# STM32-ROMI_Rev_A_1_STM32.net
KiCad netlist of a schematic drawn in Altium Designer
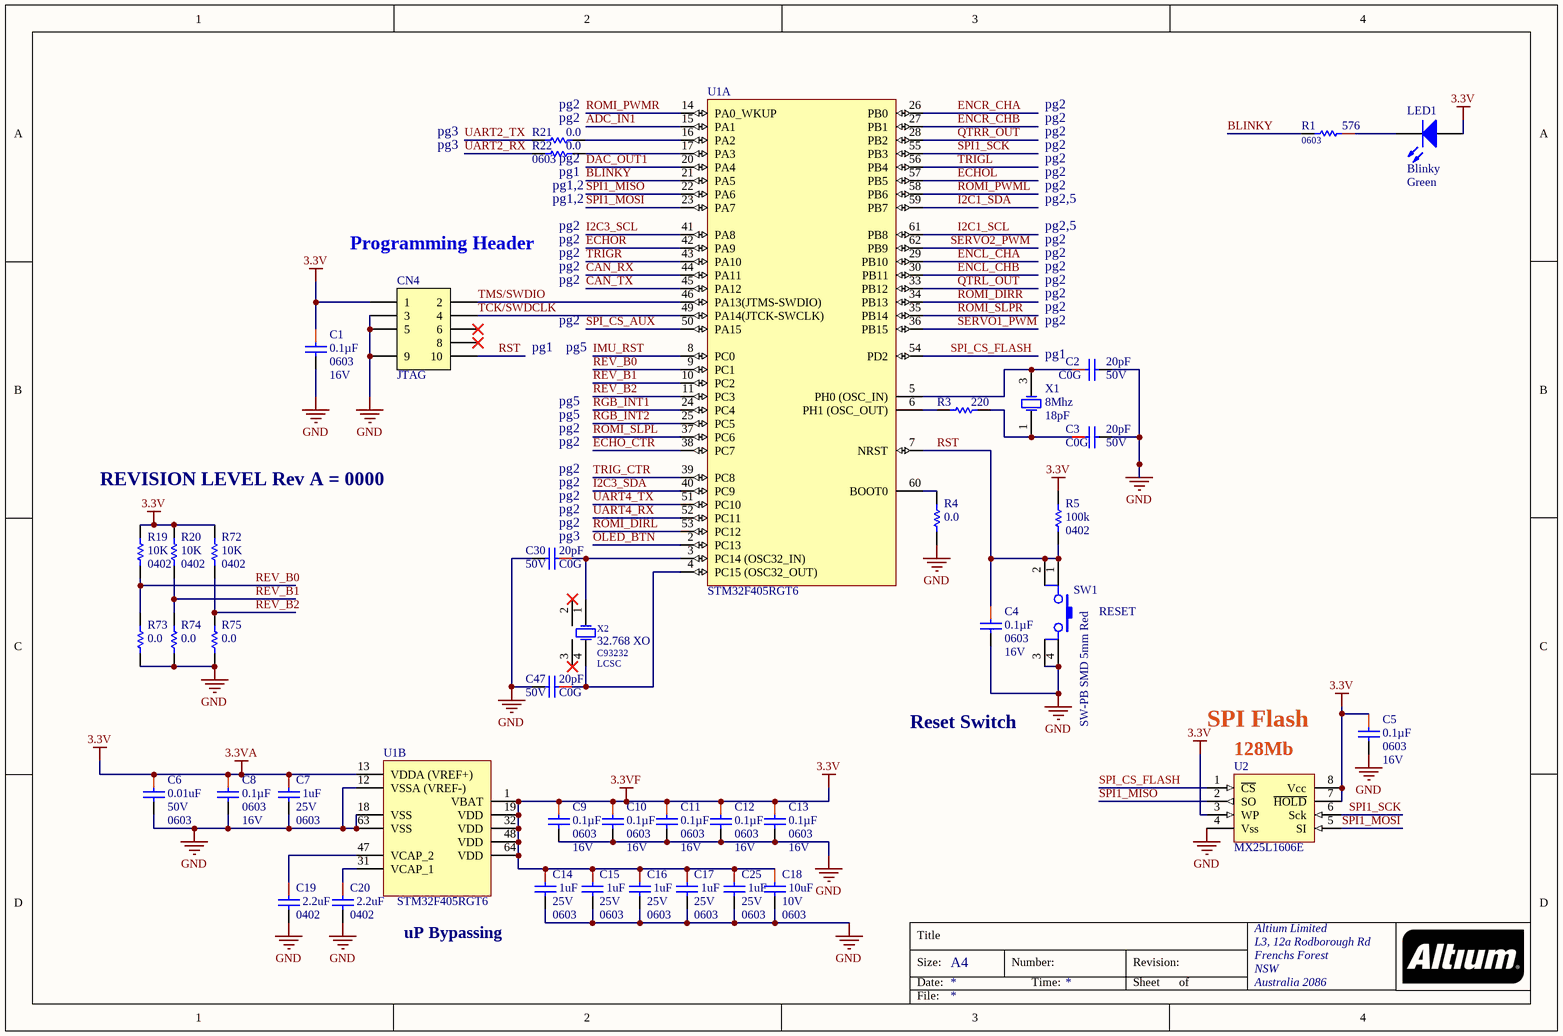
[diagram p0: STM32-ROMI_Rev_A_1_STM32.SchDoc]

(export (version "E")
  (design (tool "Eeschema 10.0.6"))
  (components
    (comp (ref "C1")
      (value "0.1uF")
      (footprint "CAPC0603(1608)_L")
      (description "0.1uF 0603 16V")
      (fields
        (field (name "MANUFACTURER") "Kemet")
        (field (name "MANUFACTURER PART NUMBER") "C0603C104K4RACTU")
        (field (name "CAPACITANCE") "0.1µF")
        (field (name "PACKAGE / CASE") "0603")
        (field (name "VOLTAGE - RATED") "16V")
      )
      (libsource (lib "JLCPCB_Passives") (part "CAP CER 0.1UF 16V 10% X7R 0603"))
    )
    (comp (ref "C2")
      (value "20pF 0402")
      (footprint "CAPC0402(1005)_L")
      (fields
        (field (name "MANUFACTURER") "Murata Electronics North America")
        (field (name "MANUFACTURER PART NUMBER") "GRM1555C1H200GA01D")
        (field (name "VOLTAGE - RATED") "50V")
        (field (name "TEMPERATURE COEFFICIENT") "C0G")
        (field (name "CAPACITANCE") "20pF")
        (field (name "TOLERANCE") "±2%")
        (field (name "CREATOR") "osman")
      )
      (libsource (lib "OLogic-Passive") (part "CAP CER 20PF 50V 2% NP0 0402"))
    )
    (comp (ref "C3")
      (value "20pF 0402")
      (footprint "CAPC0402(1005)_L")
      (fields
        (field (name "MANUFACTURER") "Murata Electronics North America")
        (field (name "MANUFACTURER PART NUMBER") "GRM1555C1H200GA01D")
        (field (name "VOLTAGE - RATED") "50V")
        (field (name "TEMPERATURE COEFFICIENT") "C0G")
        (field (name "CAPACITANCE") "20pF")
        (field (name "TOLERANCE") "±2%")
        (field (name "CREATOR") "osman")
      )
      (libsource (lib "OLogic-Passive") (part "CAP CER 20PF 50V 2% NP0 0402"))
    )
    (comp (ref "C4")
      (value "0.1uF")
      (footprint "CAPC0603(1608)_L")
      (description "0.1uF 0603 16V")
      (fields
        (field (name "MANUFACTURER") "Kemet")
        (field (name "MANUFACTURER PART NUMBER") "C0603C104K4RACTU")
        (field (name "CAPACITANCE") "0.1µF")
        (field (name "PACKAGE / CASE") "0603")
        (field (name "VOLTAGE - RATED") "16V")
      )
      (libsource (lib "JLCPCB_Passives") (part "CAP CER 0.1UF 16V 10% X7R 0603"))
    )
    (comp (ref "C5")
      (value "0.1uF")
      (footprint "CAPC0603(1608)_L")
      (description "0.1uF 0603 16V")
      (fields
        (field (name "MANUFACTURER") "Kemet")
        (field (name "MANUFACTURER PART NUMBER") "C0603C104K4RACTU")
        (field (name "CAPACITANCE") "0.1µF")
        (field (name "PACKAGE / CASE") "0603")
        (field (name "VOLTAGE - RATED") "16V")
      )
      (libsource (lib "JLCPCB_Passives") (part "CAP CER 0.1UF 16V 10% X7R 0603"))
    )
    (comp (ref "C6")
      (value "0.01uF")
      (footprint "CAPC0603(1608)_L")
      (description "0.01uF 50V 0603")
      (fields
        (field (name "MANUFACTURER") "Kemet")
        (field (name "MANUFACTURER PART NUMBER") "C0603C103K5RACTU")
        (field (name "VOLTAGE - RATED") "50V")
        (field (name "PACKAGE / CASE") "0603")
      )
      (libsource (lib "OLogic-Passive") (part "CAP CER 0.01uF 50V 10% X7R 0603"))
    )
    (comp (ref "C7")
      (value "1uF")
      (footprint "CAPC0603(1608)_N")
      (description "1uF 0603 25V")
      (fields
        (field (name "MANUFACTURER") "TDK Corporation")
        (field (name "MANUFACTURER PART NUMBER") "CGA3E1X7R1E105K080AC")
        (field (name "VOLTAGE - RATED") "25V")
        (field (name "PACKAGE / CASE") "0603")
      )
      (libsource (lib "OLogic-Passive") (part "CAP CER 1UF 25V 10% X7R 0603"))
    )
    (comp (ref "C8")
      (value "0.1uF")
      (footprint "CAPC0603(1608)_L")
      (description "0.1uF 0603 16V")
      (fields
        (field (name "MANUFACTURER") "Kemet")
        (field (name "MANUFACTURER PART NUMBER") "C0603C104K4RACTU")
        (field (name "CAPACITANCE") "0.1µF")
        (field (name "PACKAGE / CASE") "0603")
        (field (name "VOLTAGE - RATED") "16V")
      )
      (libsource (lib "JLCPCB_Passives") (part "CAP CER 0.1UF 16V 10% X7R 0603"))
    )
    (comp (ref "C9")
      (value "0.1uF")
      (footprint "CAPC0603(1608)_L")
      (description "0.1uF 0603 16V")
      (fields
        (field (name "MANUFACTURER") "Kemet")
        (field (name "MANUFACTURER PART NUMBER") "C0603C104K4RACTU")
        (field (name "CAPACITANCE") "0.1µF")
        (field (name "PACKAGE / CASE") "0603")
        (field (name "VOLTAGE - RATED") "16V")
      )
      (libsource (lib "JLCPCB_Passives") (part "CAP CER 0.1UF 16V 10% X7R 0603"))
    )
    (comp (ref "C10")
      (value "0.1uF")
      (footprint "CAPC0603(1608)_L")
      (description "0.1uF 0603 16V")
      (fields
        (field (name "MANUFACTURER") "Kemet")
        (field (name "MANUFACTURER PART NUMBER") "C0603C104K4RACTU")
        (field (name "CAPACITANCE") "0.1µF")
        (field (name "PACKAGE / CASE") "0603")
        (field (name "VOLTAGE - RATED") "16V")
      )
      (libsource (lib "JLCPCB_Passives") (part "CAP CER 0.1UF 16V 10% X7R 0603"))
    )
    (comp (ref "C11")
      (value "0.1uF")
      (footprint "CAPC0603(1608)_L")
      (description "0.1uF 0603 16V")
      (fields
        (field (name "MANUFACTURER") "Kemet")
        (field (name "MANUFACTURER PART NUMBER") "C0603C104K4RACTU")
        (field (name "CAPACITANCE") "0.1µF")
        (field (name "PACKAGE / CASE") "0603")
        (field (name "VOLTAGE - RATED") "16V")
      )
      (libsource (lib "JLCPCB_Passives") (part "CAP CER 0.1UF 16V 10% X7R 0603"))
    )
    (comp (ref "C12")
      (value "0.1uF")
      (footprint "CAPC0603(1608)_L")
      (description "0.1uF 0603 16V")
      (fields
        (field (name "MANUFACTURER") "Kemet")
        (field (name "MANUFACTURER PART NUMBER") "C0603C104K4RACTU")
        (field (name "CAPACITANCE") "0.1µF")
        (field (name "PACKAGE / CASE") "0603")
        (field (name "VOLTAGE - RATED") "16V")
      )
      (libsource (lib "JLCPCB_Passives") (part "CAP CER 0.1UF 16V 10% X7R 0603"))
    )
    (comp (ref "C13")
      (value "0.1uF")
      (footprint "CAPC0603(1608)_L")
      (description "0.1uF 0603 16V")
      (fields
        (field (name "MANUFACTURER") "Kemet")
        (field (name "MANUFACTURER PART NUMBER") "C0603C104K4RACTU")
        (field (name "CAPACITANCE") "0.1µF")
        (field (name "PACKAGE / CASE") "0603")
        (field (name "VOLTAGE - RATED") "16V")
      )
      (libsource (lib "JLCPCB_Passives") (part "CAP CER 0.1UF 16V 10% X7R 0603"))
    )
    (comp (ref "C14")
      (value "1uF")
      (footprint "CAPC0603(1608)_N")
      (description "1uF 0603 25V")
      (fields
        (field (name "MANUFACTURER") "TDK Corporation")
        (field (name "MANUFACTURER PART NUMBER") "CGA3E1X7R1E105K080AC")
        (field (name "VOLTAGE - RATED") "25V")
        (field (name "PACKAGE / CASE") "0603")
      )
      (libsource (lib "OLogic-Passive") (part "CAP CER 1UF 25V 10% X7R 0603"))
    )
    (comp (ref "C15")
      (value "1uF")
      (footprint "CAPC0603(1608)_N")
      (description "1uF 0603 25V")
      (fields
        (field (name "MANUFACTURER") "TDK Corporation")
        (field (name "MANUFACTURER PART NUMBER") "CGA3E1X7R1E105K080AC")
        (field (name "VOLTAGE - RATED") "25V")
        (field (name "PACKAGE / CASE") "0603")
      )
      (libsource (lib "OLogic-Passive") (part "CAP CER 1UF 25V 10% X7R 0603"))
    )
    (comp (ref "C16")
      (value "1uF")
      (footprint "CAPC0603(1608)_N")
      (description "1uF 0603 25V")
      (fields
        (field (name "MANUFACTURER") "TDK Corporation")
        (field (name "MANUFACTURER PART NUMBER") "CGA3E1X7R1E105K080AC")
        (field (name "VOLTAGE - RATED") "25V")
        (field (name "PACKAGE / CASE") "0603")
      )
      (libsource (lib "OLogic-Passive") (part "CAP CER 1UF 25V 10% X7R 0603"))
    )
    (comp (ref "C17")
      (value "1uF")
      (footprint "CAPC0603(1608)_N")
      (description "1uF 0603 25V")
      (fields
        (field (name "MANUFACTURER") "TDK Corporation")
        (field (name "MANUFACTURER PART NUMBER") "CGA3E1X7R1E105K080AC")
        (field (name "VOLTAGE - RATED") "25V")
        (field (name "PACKAGE / CASE") "0603")
      )
      (libsource (lib "OLogic-Passive") (part "CAP CER 1UF 25V 10% X7R 0603"))
    )
    (comp (ref "C18")
      (value "10uF")
      (footprint "CAPC0603(1608)_L")
      (description "10uF 0603 10V")
      (fields
        (field (name "MANUFACTURER") "Taiyo Yuden")
        (field (name "MANUFACTURER PART NUMBER") "LMK107BBJ106MAHT")
        (field (name "VOLTAGE - RATED") "10V")
        (field (name "PACKAGE / CASE") "0603")
      )
      (libsource (lib "OLogic-Passive") (part "CAP CER 10UF 10V 20% X5R 0603"))
    )
    (comp (ref "C19")
      (value "2.2uF")
      (footprint "CAPC0402(1005)_L")
      (description "2.2uF 0402")
      (fields
        (field (name "MANUFACTURER") "TDK Corporation")
        (field (name "MANUFACTURER PART NUMBER") "C1005X5R1V225K050BC")
        (field (name "PACKAGE / CASE") "0402")
        (field (name "CREATOR") "osman")
      )
      (libsource (lib "OLogic-Passive") (part "CAP CER 2.2UF 35V 10% X5R 0402"))
    )
    (comp (ref "C20")
      (value "2.2uF")
      (footprint "CAPC0402(1005)_L")
      (description "2.2uF 0402")
      (fields
        (field (name "MANUFACTURER") "TDK Corporation")
        (field (name "MANUFACTURER PART NUMBER") "C1005X5R1V225K050BC")
        (field (name "PACKAGE / CASE") "0402")
        (field (name "CREATOR") "osman")
      )
      (libsource (lib "OLogic-Passive") (part "CAP CER 2.2UF 35V 10% X5R 0402"))
    )
    (comp (ref "C25")
      (value "1uF")
      (footprint "CAPC0603(1608)_N")
      (description "1uF 0603 25V")
      (fields
        (field (name "MANUFACTURER") "TDK Corporation")
        (field (name "MANUFACTURER PART NUMBER") "CGA3E1X7R1E105K080AC")
        (field (name "VOLTAGE - RATED") "25V")
        (field (name "PACKAGE / CASE") "0603")
      )
      (libsource (lib "OLogic-Passive") (part "CAP CER 1UF 25V 10% X7R 0603"))
    )
    (comp (ref "C30")
      (value "20pF 0402")
      (footprint "CAPC0402(1005)_L")
      (fields
        (field (name "MANUFACTURER") "Murata Electronics North America")
        (field (name "MANUFACTURER PART NUMBER") "GRM1555C1H200GA01D")
        (field (name "VOLTAGE - RATED") "50V")
        (field (name "TEMPERATURE COEFFICIENT") "C0G")
        (field (name "CAPACITANCE") "20pF")
        (field (name "TOLERANCE") "±2%")
        (field (name "CREATOR") "osman")
      )
      (libsource (lib "OLogic-Passive") (part "CAP CER 20PF 50V 2% NP0 0402"))
    )
    (comp (ref "C47")
      (value "20pF 0402")
      (footprint "CAPC0402(1005)_L")
      (fields
        (field (name "MANUFACTURER") "Murata Electronics North America")
        (field (name "MANUFACTURER PART NUMBER") "GRM1555C1H200GA01D")
        (field (name "VOLTAGE - RATED") "50V")
        (field (name "TEMPERATURE COEFFICIENT") "C0G")
        (field (name "CAPACITANCE") "20pF")
        (field (name "TOLERANCE") "±2%")
        (field (name "CREATOR") "osman")
      )
      (libsource (lib "OLogic-Passive") (part "CAP CER 20PF 50V 2% NP0 0402"))
    )
    (comp (ref "CN4")
      (value "JTAG")
      (footprint "BOBS FAVORITE DEBUG HDR")
      (description "SAMTEC - FTSH-105-01-L-DV - HEADER, 1.27MM, SMD, 10WAY")
      (fields (field (name "MANUFACTURER") "Samtec") (field (name "MPN") "FTSH-105-01-L-DV"))
      (libsource (lib "OLogic-Connectors") (part "CONN-2x5-SWD"))
    )
    (comp (ref "LED1")
      (value "Blinky")
      (footprint "SM-LED-0603")
      (description "LED GREEN CLEAR THIN 0603 SMD")
      (fields
        (field (name "MANUFACTURER") "Lite-On Inc")
        (field (name "MANUFACTURER PART NUMBER") "LTST-C191KGKT")
        (field (name "COLOR") "Green")
      )
      (libsource (lib "Kyle-Diode-Opto-LED") (part "LTST-C191KGKT"))
    )
    (comp (ref "R1")
      (value "576")
      (footprint "RESC0603(1608)_N")
      (description "576OHMS ±1% 1/10W 0603")
      (fields (field (name "MANUFACTURER PART NUMBER") "0603WAF5760T5E") (field (name "PART SIZE") "0603"))
      (libsource (lib "JLCPCB_Passives") (part "576"))
    )
    (comp (ref "R3")
      (value "220")
      (footprint "RESC0402(1005)_L")
      (description "220 0402")
      (fields
        (field (name "MANUFACTURER") "Panasonic Electronic Components")
        (field (name "MANUFACTURER PART NUMBER") "ERJ-2RKF2200X")
        (field (name "RESISTANCE (OHMS)") "220")
        (field (name "CREATOR") "osman")
      )
      (libsource (lib "OLogic-Passive") (part "RES 220 OHM 1% 1/10W 0402"))
    )
    (comp (ref "R4")
      (value "0")
      (footprint "RESC0402(1005)_L")
      (description "0.0 0402")
      (fields
        (field (name "MANUFACTURER") "Panasonic Electronic Components")
        (field (name "MANUFACTURER PART NUMBER") "ERJ-2GE0R00X")
        (field (name "RESISTANCE (OHMS)") "0.0")
        (field (name "CREATOR") "osman")
      )
      (libsource (lib "OLogic-Passive") (part "RES 0.0 OHM JUMPER 1/10W 0402"))
    )
    (comp (ref "R5")
      (value "100K 0402")
      (footprint "RESC0402(1005)_L")
      (fields
        (field (name "MANUFACTURER") "Yageo")
        (field (name "MANUFACTURER PART NUMBER") "RC0402FR-07100KL")
        (field (name "TOLERANCE") "±1%")
        (field (name "SUPPLIER DEVICE PACKAGE") "0402")
        (field (name "RESISTANCE (OHMS)") "100k")
      )
      (libsource (lib "OLogic-Passive") (part "RES 100K OHM 1% 1/16W 0402"))
    )
    (comp (ref "R19")
      (value "10K")
      (footprint "RESC0402(1005)_N")
      (description "10K 0402")
      (fields
        (field (name "MANUFACTURER") "Samsung Electro-Mechanics")
        (field (name "MANUFACTURER PART NUMBER") "RC1005F103CS")
        (field (name "SUPPLIER DEVICE PACKAGE") "0402")
      )
      (libsource (lib "OLogic-Passive") (part "RES 10K OHM 1% 1/16W 0402"))
    )
    (comp (ref "R20")
      (value "10K")
      (footprint "RESC0402(1005)_N")
      (description "10K 0402")
      (fields
        (field (name "MANUFACTURER") "Samsung Electro-Mechanics")
        (field (name "MANUFACTURER PART NUMBER") "RC1005F103CS")
        (field (name "SUPPLIER DEVICE PACKAGE") "0402")
      )
      (libsource (lib "OLogic-Passive") (part "RES 10K OHM 1% 1/16W 0402"))
    )
    (comp (ref "R21")
      (value "0 0603")
      (footprint "RESC0603(1608)_N")
      (fields
        (field (name "MANUFACTURER") "Vishay Dale")
        (field (name "MANUFACTURER PART NUMBER") "CRCW06030000Z0EAHP")
        (field (name "TOLERANCE") "Jumper")
        (field (name "RESISTANCE (OHMS)") "0.0")
      )
      (libsource (lib "OLogic-Passive") (part "RES 0.0 OHM 1/4W JUMP 0603 SMD"))
    )
    (comp (ref "R22")
      (value "0 0603")
      (footprint "RESC0603(1608)_N")
      (fields
        (field (name "MANUFACTURER") "Vishay Dale")
        (field (name "MANUFACTURER PART NUMBER") "CRCW06030000Z0EAHP")
        (field (name "TOLERANCE") "Jumper")
        (field (name "RESISTANCE (OHMS)") "0.0")
        (field (name "PACKAGE / CASE") "0603")
      )
      (libsource (lib "OLogic-Passive") (part "RES 0.0 OHM 1/4W JUMP 0603 SMD"))
    )
    (comp (ref "R72")
      (value "10K")
      (footprint "RESC0402(1005)_N")
      (description "10K 0402")
      (fields
        (field (name "MANUFACTURER") "Samsung Electro-Mechanics")
        (field (name "MANUFACTURER PART NUMBER") "RC1005F103CS")
        (field (name "SUPPLIER DEVICE PACKAGE") "0402")
      )
      (libsource (lib "OLogic-Passive") (part "RES 10K OHM 1% 1/16W 0402"))
    )
    (comp (ref "R73")
      (value "0")
      (footprint "RESC0402(1005)_L")
      (description "0.0 0402")
      (fields
        (field (name "MANUFACTURER") "Panasonic Electronic Components")
        (field (name "MANUFACTURER PART NUMBER") "ERJ-2GE0R00X")
        (field (name "RESISTANCE (OHMS)") "0.0")
        (field (name "CREATOR") "osman")
      )
      (libsource (lib "OLogic-Passive") (part "RES 0.0 OHM JUMPER 1/10W 0402"))
    )
    (comp (ref "R74")
      (value "0")
      (footprint "RESC0402(1005)_L")
      (description "0.0 0402")
      (fields
        (field (name "MANUFACTURER") "Panasonic Electronic Components")
        (field (name "MANUFACTURER PART NUMBER") "ERJ-2GE0R00X")
        (field (name "RESISTANCE (OHMS)") "0.0")
        (field (name "CREATOR") "osman")
      )
      (libsource (lib "OLogic-Passive") (part "RES 0.0 OHM JUMPER 1/10W 0402"))
    )
    (comp (ref "R75")
      (value "0")
      (footprint "RESC0402(1005)_L")
      (description "0.0 0402")
      (fields
        (field (name "MANUFACTURER") "Panasonic Electronic Components")
        (field (name "MANUFACTURER PART NUMBER") "ERJ-2GE0R00X")
        (field (name "RESISTANCE (OHMS)") "0.0")
        (field (name "CREATOR") "osman")
      )
      (libsource (lib "OLogic-Passive") (part "RES 0.0 OHM JUMPER 1/10W 0402"))
    )
    (comp (ref "SW1")
      (value "RESET")
      (footprint "SW TACT Red 6mm x 6mm")
      (description "SWITCH TACTILE SPST-NO 0.05A 12V")
      (fields
        (field (name "MANUFACTURER") "C&K Components")
        (field (name "MANUFACTURER PART NUMBER") "PTS645SK50SMTR92 LFS")
        (field (name "TEXT") "SW-PB SMD 5mm Red")
        (field (name "PUBLISHER") "Altium Limited")
      )
      (libsource (lib "OLogic-Switches") (part "SW-PB SMD 5mm Red"))
    )
    (comp (ref "U1")
      (value "STM32F405RGT6")
      (footprint "STM-LQFP64_N")
      (description "IC MCU 32BIT 1MB FLASH 64LQFP")
      (fields
        (field (name "MANUFACTURER") "STMicroelectronics")
        (field (name "MANUFACTURER PART NUMBER") "STM32F405RGT6")
      )
      (libsource (lib "OLogic-CPU-Memory") (part "STM32F405RGT6"))
    )
    (comp (ref "U2")
      (value "MX25L1606E")
      (footprint "SOG.050/8D")
      (description "16M NOR Flash")
      (fields (field (name "MANUFACTURER") "Macronix") (field (name "MPN") "MX25L1606EM2I-12G"))
      (libsource (lib "OLogic-CPU-Memory") (part "MX25L1606E"))
    )
    (comp (ref "X1")
      (value "8Mhz")
      (footprint "SMXOSC/5x3.2")
      (description "8Mhz ABM3 Parallel Load Crystal")
      (fields
        (field (name "MANUFACTURER") "Abracon Corporation")
        (field (name "MANUFACTURER PART NUMBER") "ABM3B-8.000MHZ-B2-T")
        (field (name "LOAD CAPACITANCE") "18pF")
      )
      (libsource (lib "OLogic-RF-Osc") (part "CRYSTAL 8MHZ ABM3"))
    )
    (comp (ref "X2")
      (value "32.768 XO")
      (footprint "OSCABS")
      (description "SMD CRYSTAL RESONATORS 32.768KHZ ±20PPM SMD-3215_2P ROHS")
      (fields (field (name "SUPPLIER PART NUMBER 2") "C93232") (field (name "SUPPLIER 2") "LCSC"))
      (libsource (lib "JLCPCB_RF-OSC") (part "DST310S 32.768KHz"))
    )
  )
  (nets
    (net (code "1") (name "/ADC_IN1") (class "Default")
      (node (ref "U1") (pin "15") (pinfunction "PA1_15") (pintype "bidirectional"))
    )
    (net (code "2") (name "/BLINKY") (class "Default")
      (node (ref "R1") (pin "2") (pinfunction "2_2") (pintype "passive"))
      (node (ref "U1") (pin "21") (pinfunction "PA5_21") (pintype "bidirectional"))
    )
    (net (code "3") (name "/CAN_RX") (class "Default")
      (node (ref "U1") (pin "44") (pinfunction "PA11_44") (pintype "bidirectional"))
    )
    (net (code "4") (name "/CAN_TX") (class "Default")
      (node (ref "U1") (pin "45") (pinfunction "PA12_45") (pintype "bidirectional"))
    )
    (net (code "5") (name "/DAC_OUT1") (class "Default")
      (node (ref "U1") (pin "20") (pinfunction "PA4_20") (pintype "bidirectional"))
    )
    (net (code "6") (name "/ECHOL") (class "Default")
      (node (ref "U1") (pin "57") (pinfunction "PB5_57") (pintype "bidirectional"))
    )
    (net (code "7") (name "/ECHOR") (class "Default")
      (node (ref "U1") (pin "42") (pinfunction "PA9_42") (pintype "bidirectional"))
    )
    (net (code "8") (name "/ECHO_CTR") (class "Default")
      (node (ref "U1") (pin "38") (pinfunction "PC7_38") (pintype "bidirectional"))
    )
    (net (code "9") (name "/ENCL_CHA") (class "Default")
      (node (ref "U1") (pin "29") (pinfunction "PB10_29") (pintype "bidirectional"))
    )
    (net (code "10") (name "/ENCL_CHB") (class "Default")
      (node (ref "U1") (pin "30") (pinfunction "PB11_30") (pintype "bidirectional"))
    )
    (net (code "11") (name "/ENCR_CHA") (class "Default")
      (node (ref "U1") (pin "26") (pinfunction "PB0_26") (pintype "bidirectional"))
    )
    (net (code "12") (name "/ENCR_CHB") (class "Default")
      (node (ref "U1") (pin "27") (pinfunction "PB1_27") (pintype "bidirectional"))
    )
    (net (code "13") (name "/I2C1_SCL") (class "Default")
      (node (ref "U1") (pin "61") (pinfunction "PB8_61") (pintype "bidirectional"))
    )
    (net (code "14") (name "/I2C1_SDA") (class "Default")
      (node (ref "U1") (pin "59") (pinfunction "PB7_59") (pintype "bidirectional"))
    )
    (net (code "15") (name "/I2C3_SCL") (class "Default")
      (node (ref "U1") (pin "41") (pinfunction "PA8_41") (pintype "bidirectional"))
    )
    (net (code "16") (name "/I2C3_SDA") (class "Default")
      (node (ref "U1") (pin "40") (pinfunction "PC9_40") (pintype "bidirectional"))
    )
    (net (code "17") (name "/IMU_RST") (class "Default")
      (node (ref "U1") (pin "8") (pinfunction "PC0_8") (pintype "bidirectional"))
    )
    (net (code "18") (name "/OLED_BTN") (class "Default")
      (node (ref "U1") (pin "2") (pinfunction "PC13_2") (pintype "bidirectional"))
    )
    (net (code "19") (name "/QTRL_OUT") (class "Default")
      (node (ref "U1") (pin "33") (pinfunction "PB12_33") (pintype "bidirectional"))
    )
    (net (code "20") (name "/QTRR_OUT") (class "Default")
      (node (ref "U1") (pin "28") (pinfunction "PB2_28") (pintype "bidirectional"))
    )
    (net (code "21") (name "/REV_B0") (class "Default")
      (node (ref "R19") (pin "1") (pinfunction "1_1") (pintype "passive"))
      (node (ref "R73") (pin "2") (pinfunction "2_2") (pintype "passive"))
      (node (ref "U1") (pin "9") (pinfunction "PC1_9") (pintype "bidirectional"))
    )
    (net (code "22") (name "/REV_B1") (class "Default")
      (node (ref "R20") (pin "1") (pinfunction "1_1") (pintype "passive"))
      (node (ref "R74") (pin "2") (pinfunction "2_2") (pintype "passive"))
      (node (ref "U1") (pin "10") (pinfunction "PC2_10") (pintype "bidirectional"))
    )
    (net (code "23") (name "/REV_B2") (class "Default")
      (node (ref "R72") (pin "1") (pinfunction "1_1") (pintype "passive"))
      (node (ref "R75") (pin "2") (pinfunction "2_2") (pintype "passive"))
      (node (ref "U1") (pin "11") (pinfunction "PC3_11") (pintype "bidirectional"))
    )
    (net (code "24") (name "/RGB_INT1") (class "Default")
      (node (ref "U1") (pin "24") (pinfunction "PC4_24") (pintype "bidirectional"))
    )
    (net (code "25") (name "/RGB_INT2") (class "Default")
      (node (ref "U1") (pin "25") (pinfunction "PC5_25") (pintype "bidirectional"))
    )
    (net (code "26") (name "/ROMI_DIRL") (class "Default")
      (node (ref "U1") (pin "53") (pinfunction "PC12_53") (pintype "bidirectional"))
    )
    (net (code "27") (name "/ROMI_DIRR") (class "Default")
      (node (ref "U1") (pin "34") (pinfunction "PB13_34") (pintype "bidirectional"))
    )
    (net (code "28") (name "/ROMI_PWML") (class "Default")
      (node (ref "U1") (pin "58") (pinfunction "PB6_58") (pintype "bidirectional"))
    )
    (net (code "29") (name "/ROMI_PWMR") (class "Default")
      (node (ref "U1") (pin "14") (pinfunction "PA0_WKUP_14") (pintype "bidirectional"))
    )
    (net (code "30") (name "/ROMI_~{SLPL}") (class "Default")
      (node (ref "U1") (pin "37") (pinfunction "PC6_37") (pintype "bidirectional"))
    )
    (net (code "31") (name "/ROMI_~{SLPR}") (class "Default")
      (node (ref "U1") (pin "35") (pinfunction "PB14_35") (pintype "bidirectional"))
    )
    (net (code "32") (name "/RST") (class "Default")
      (node (ref "C4") (pin "1") (pinfunction "1_1") (pintype "passive"))
      (node (ref "CN4") (pin "10") (pinfunction "10_10") (pintype "passive"))
      (node (ref "R5") (pin "1") (pinfunction "1_1") (pintype "passive"))
      (node (ref "SW1") (pin "1") (pinfunction "1_1") (pintype "passive"))
      (node (ref "SW1") (pin "2") (pinfunction "2_2") (pintype "passive"))
      (node (ref "U1") (pin "7") (pinfunction "NRST_7") (pintype "bidirectional"))
    )
    (net (code "33") (name "/SERVO1_PWM") (class "Default")
      (node (ref "U1") (pin "36") (pinfunction "PB15_36") (pintype "bidirectional"))
    )
    (net (code "34") (name "/SERVO2_PWM") (class "Default")
      (node (ref "U1") (pin "62") (pinfunction "PB9_62") (pintype "bidirectional"))
    )
    (net (code "35") (name "/SPI1_MISO") (class "Default")
      (node (ref "U1") (pin "22") (pinfunction "PA6_22") (pintype "bidirectional"))
      (node (ref "U2") (pin "2") (pinfunction "SO_2") (pintype "output"))
    )
    (net (code "36") (name "/SPI1_MOSI") (class "Default")
      (node (ref "U1") (pin "23") (pinfunction "PA7_23") (pintype "bidirectional"))
      (node (ref "U2") (pin "5") (pinfunction "SI_5") (pintype "input"))
    )
    (net (code "37") (name "/SPI1_SCK") (class "Default")
      (node (ref "U1") (pin "55") (pinfunction "PB3_55") (pintype "bidirectional"))
      (node (ref "U2") (pin "6") (pinfunction "Sck_6") (pintype "input"))
    )
    (net (code "38") (name "/SPI_CS_AUX") (class "Default")
      (node (ref "U1") (pin "50") (pinfunction "PA15_50") (pintype "bidirectional"))
    )
    (net (code "39") (name "/SPI_CS_FLASH") (class "Default")
      (node (ref "U1") (pin "54") (pinfunction "PD2_54") (pintype "bidirectional"))
      (node (ref "U2") (pin "1") (pinfunction "~{CS}_1") (pintype "input"))
    )
    (net (code "40") (name "/TCK{slash}SWDCLK") (class "Default")
      (node (ref "CN4") (pin "4") (pinfunction "4_4") (pintype "passive"))
      (node (ref "U1") (pin "49") (pinfunction "PA14(JTCK-SWCLK)_49") (pintype "bidirectional"))
    )
    (net (code "41") (name "/TMS{slash}SWDIO") (class "Default")
      (node (ref "CN4") (pin "2") (pinfunction "2_2") (pintype "passive"))
      (node (ref "U1") (pin "46") (pinfunction "PA13(JTMS-SWDIO)_46") (pintype "bidirectional"))
    )
    (net (code "42") (name "/TRIGL") (class "Default")
      (node (ref "U1") (pin "56") (pinfunction "PB4_56") (pintype "bidirectional"))
    )
    (net (code "43") (name "/TRIGR") (class "Default")
      (node (ref "U1") (pin "43") (pinfunction "PA10_43") (pintype "bidirectional"))
    )
    (net (code "44") (name "/TRIG_CTR") (class "Default")
      (node (ref "U1") (pin "39") (pinfunction "PC8_39") (pintype "bidirectional"))
    )
    (net (code "45") (name "/UART2_RX") (class "Default")
      (node (ref "R22") (pin "2") (pinfunction "2_2") (pintype "passive"))
    )
    (net (code "46") (name "/UART2_TX") (class "Default")
      (node (ref "R21") (pin "2") (pinfunction "2_2") (pintype "passive"))
    )
    (net (code "47") (name "/UART4_RX") (class "Default")
      (node (ref "U1") (pin "52") (pinfunction "PC11_52") (pintype "bidirectional"))
    )
    (net (code "48") (name "/UART4_TX") (class "Default")
      (node (ref "U1") (pin "51") (pinfunction "PC10_51") (pintype "bidirectional"))
    )
    (net (code "49") (name "3.3V") (class "Default")
      (node (ref "C1") (pin "1") (pinfunction "1_1") (pintype "passive"))
      (node (ref "C10") (pin "1") (pinfunction "1_1") (pintype "passive"))
      (node (ref "C11") (pin "1") (pinfunction "1_1") (pintype "passive"))
      (node (ref "C12") (pin "1") (pinfunction "1_1") (pintype "passive"))
      (node (ref "C13") (pin "1") (pinfunction "1_1") (pintype "passive"))
      (node (ref "C14") (pin "1") (pinfunction "1_1") (pintype "passive"))
      (node (ref "C15") (pin "1") (pinfunction "1_1") (pintype "passive"))
      (node (ref "C16") (pin "1") (pinfunction "1_1") (pintype "passive"))
      (node (ref "C17") (pin "1") (pinfunction "1_1") (pintype "passive"))
      (node (ref "C18") (pin "1") (pinfunction "1_1") (pintype "passive"))
      (node (ref "C25") (pin "1") (pinfunction "1_1") (pintype "passive"))
      (node (ref "C5") (pin "1") (pinfunction "1_1") (pintype "passive"))
      (node (ref "C6") (pin "1") (pinfunction "1_1") (pintype "passive"))
      (node (ref "C7") (pin "1") (pinfunction "1_1") (pintype "passive"))
      (node (ref "C8") (pin "1") (pinfunction "1_1") (pintype "passive"))
      (node (ref "C9") (pin "1") (pinfunction "1_1") (pintype "passive"))
      (node (ref "CN4") (pin "1") (pinfunction "1_1") (pintype "passive"))
      (node (ref "LED1") (pin "1") (pinfunction "1_1") (pintype "passive"))
      (node (ref "R19") (pin "2") (pinfunction "2_2") (pintype "passive"))
      (node (ref "R20") (pin "2") (pinfunction "2_2") (pintype "passive"))
      (node (ref "R5") (pin "2") (pinfunction "2_2") (pintype "passive"))
      (node (ref "R72") (pin "2") (pinfunction "2_2") (pintype "passive"))
      (node (ref "U1") (pin "1") (pinfunction "VBAT_1") (pintype "power_in"))
      (node (ref "U1") (pin "13") (pinfunction "VDDA_(VREF+)_13") (pintype "power_in"))
      (node (ref "U1") (pin "19") (pinfunction "VDD_19") (pintype "power_in"))
      (node (ref "U1") (pin "32") (pinfunction "VDD_32") (pintype "power_in"))
      (node (ref "U1") (pin "48") (pinfunction "VDD_48") (pintype "power_in"))
      (node (ref "U1") (pin "64") (pinfunction "VDD_64") (pintype "power_in"))
      (node (ref "U2") (pin "3") (pinfunction "WP_3") (pintype "input"))
      (node (ref "U2") (pin "7") (pinfunction "~{HOLD}_7") (pintype "passive"))
      (node (ref "U2") (pin "8") (pinfunction "Vcc_8") (pintype "power_in"))
    )
    (net (code "50") (name "GND") (class "Default")
      (node (ref "C1") (pin "2") (pinfunction "2_2") (pintype "passive"))
      (node (ref "C10") (pin "2") (pinfunction "2_2") (pintype "passive"))
      (node (ref "C11") (pin "2") (pinfunction "2_2") (pintype "passive"))
      (node (ref "C12") (pin "2") (pinfunction "2_2") (pintype "passive"))
      (node (ref "C13") (pin "2") (pinfunction "2_2") (pintype "passive"))
      (node (ref "C14") (pin "2") (pinfunction "2_2") (pintype "passive"))
      (node (ref "C15") (pin "2") (pinfunction "2_2") (pintype "passive"))
      (node (ref "C16") (pin "2") (pinfunction "2_2") (pintype "passive"))
      (node (ref "C17") (pin "2") (pinfunction "2_2") (pintype "passive"))
      (node (ref "C18") (pin "2") (pinfunction "2_2") (pintype "passive"))
      (node (ref "C19") (pin "2") (pinfunction "2_2") (pintype "passive"))
      (node (ref "C2") (pin "2") (pinfunction "2_2") (pintype "passive"))
      (node (ref "C20") (pin "2") (pinfunction "2_2") (pintype "passive"))
      (node (ref "C25") (pin "2") (pinfunction "2_2") (pintype "passive"))
      (node (ref "C3") (pin "2") (pinfunction "2_2") (pintype "passive"))
      (node (ref "C30") (pin "2") (pinfunction "2_2") (pintype "passive"))
      (node (ref "C4") (pin "2") (pinfunction "2_2") (pintype "passive"))
      (node (ref "C47") (pin "2") (pinfunction "2_2") (pintype "passive"))
      (node (ref "C5") (pin "2") (pinfunction "2_2") (pintype "passive"))
      (node (ref "C6") (pin "2") (pinfunction "2_2") (pintype "passive"))
      (node (ref "C7") (pin "2") (pinfunction "2_2") (pintype "passive"))
      (node (ref "C8") (pin "2") (pinfunction "2_2") (pintype "passive"))
      (node (ref "C9") (pin "2") (pinfunction "2_2") (pintype "passive"))
      (node (ref "CN4") (pin "3") (pinfunction "3_3") (pintype "passive"))
      (node (ref "CN4") (pin "5") (pinfunction "5_5") (pintype "passive"))
      (node (ref "CN4") (pin "9") (pinfunction "9_9") (pintype "passive"))
      (node (ref "R4") (pin "1") (pinfunction "1_1") (pintype "passive"))
      (node (ref "R73") (pin "1") (pinfunction "1_1") (pintype "passive"))
      (node (ref "R74") (pin "1") (pinfunction "1_1") (pintype "passive"))
      (node (ref "R75") (pin "1") (pinfunction "1_1") (pintype "passive"))
      (node (ref "SW1") (pin "3") (pinfunction "3_3") (pintype "passive"))
      (node (ref "SW1") (pin "4") (pinfunction "4_4") (pintype "passive"))
      (node (ref "U1") (pin "12") (pinfunction "VSSA_(VREF-)_12") (pintype "power_in"))
      (node (ref "U1") (pin "18") (pinfunction "VSS_18") (pintype "power_in"))
      (node (ref "U1") (pin "63") (pinfunction "VSS_63") (pintype "power_in"))
      (node (ref "U2") (pin "4") (pinfunction "Vss_4") (pintype "power_in"))
    )
    (net (code "51") (name "Net-(LED1-Pad2)") (class "Default")
      (node (ref "LED1") (pin "2") (pinfunction "2_2") (pintype "passive"))
      (node (ref "R1") (pin "1") (pinfunction "1_1") (pintype "passive"))
    )
    (net (code "52") (name "Net-(U1A-BOOT0)") (class "Default")
      (node (ref "R4") (pin "2") (pinfunction "2_2") (pintype "passive"))
      (node (ref "U1") (pin "60") (pinfunction "BOOT0_60") (pintype "passive"))
    )
    (net (code "53") (name "Net-(U1A-PA2)") (class "Default")
      (node (ref "R21") (pin "1") (pinfunction "1_1") (pintype "passive"))
      (node (ref "U1") (pin "16") (pinfunction "PA2_16") (pintype "bidirectional"))
    )
    (net (code "54") (name "Net-(U1A-PA3)") (class "Default")
      (node (ref "R22") (pin "1") (pinfunction "1_1") (pintype "passive"))
      (node (ref "U1") (pin "17") (pinfunction "PA3_17") (pintype "bidirectional"))
    )
    (net (code "55") (name "Net-(U1A-PC14_(OSC32_IN))") (class "Default")
      (node (ref "C30") (pin "1") (pinfunction "1_1") (pintype "passive"))
      (node (ref "U1") (pin "3") (pinfunction "PC14_(OSC32_IN)_3") (pintype "bidirectional"))
      (node (ref "X2") (pin "1") (pinfunction "OSC1_1") (pintype "passive"))
    )
    (net (code "56") (name "Net-(U1A-PC15_(OSC32_OUT))") (class "Default")
      (node (ref "C47") (pin "1") (pinfunction "1_1") (pintype "passive"))
      (node (ref "U1") (pin "4") (pinfunction "PC15_(OSC32_OUT)_4") (pintype "bidirectional"))
      (node (ref "X2") (pin "4") (pinfunction "OSC2_4") (pintype "passive"))
    )
    (net (code "57") (name "Net-(U1A-PH0_(OSC_IN))") (class "Default")
      (node (ref "C2") (pin "1") (pinfunction "1_1") (pintype "passive"))
      (node (ref "U1") (pin "5") (pinfunction "PH0_(OSC_IN)_5") (pintype "passive"))
      (node (ref "X1") (pin "3") (pinfunction "OSC2_3") (pintype "passive"))
    )
    (net (code "58") (name "Net-(U1A-PH1_(OSC_OUT))") (class "Default")
      (node (ref "R3") (pin "2") (pinfunction "2_2") (pintype "passive"))
      (node (ref "U1") (pin "6") (pinfunction "PH1_(OSC_OUT)_6") (pintype "passive"))
    )
    (net (code "59") (name "Net-(U1B-VCAP_1)") (class "Default")
      (node (ref "C20") (pin "1") (pinfunction "1_1") (pintype "passive"))
      (node (ref "U1") (pin "31") (pinfunction "VCAP_1_31") (pintype "passive"))
    )
    (net (code "60") (name "Net-(U1B-VCAP_2)") (class "Default")
      (node (ref "C19") (pin "1") (pinfunction "1_1") (pintype "passive"))
      (node (ref "U1") (pin "47") (pinfunction "VCAP_2_47") (pintype "passive"))
    )
    (net (code "61") (name "Net-(X1-OSC1)") (class "Default")
      (node (ref "C3") (pin "1") (pinfunction "1_1") (pintype "passive"))
      (node (ref "R3") (pin "1") (pinfunction "1_1") (pintype "passive"))
      (node (ref "X1") (pin "1") (pinfunction "OSC1_1") (pintype "passive"))
    )
    (net (code "62") (name "unconnected-(CN4-Pad6)") (class "Default")
      (node (ref "CN4") (pin "6") (pinfunction "6_6") (pintype "passive+no_connect"))
    )
    (net (code "63") (name "unconnected-(CN4-Pad8)") (class "Default")
      (node (ref "CN4") (pin "8") (pinfunction "8_8") (pintype "passive+no_connect"))
    )
    (net (code "64") (name "unconnected-(X1-NC-Pad2)") (class "Default")
      (node (ref "X1") (pin "2") (pinfunction "NC_2") (pintype "passive"))
    )
    (net (code "65") (name "unconnected-(X1-NC-Pad4)") (class "Default")
      (node (ref "X1") (pin "4") (pinfunction "NC_4") (pintype "passive"))
    )
    (net (code "66") (name "unconnected-(X2-NC-Pad2)") (class "Default")
      (node (ref "X2") (pin "2") (pinfunction "NC_2") (pintype "passive+no_connect"))
    )
    (net (code "67") (name "unconnected-(X2-NC-Pad3)") (class "Default")
      (node (ref "X2") (pin "3") (pinfunction "NC_3") (pintype "passive+no_connect"))
    )
  )
)
